# 2021_Design_Sch_PilotCity.net
KiCad netlist of a schematic drawn in EAGLE
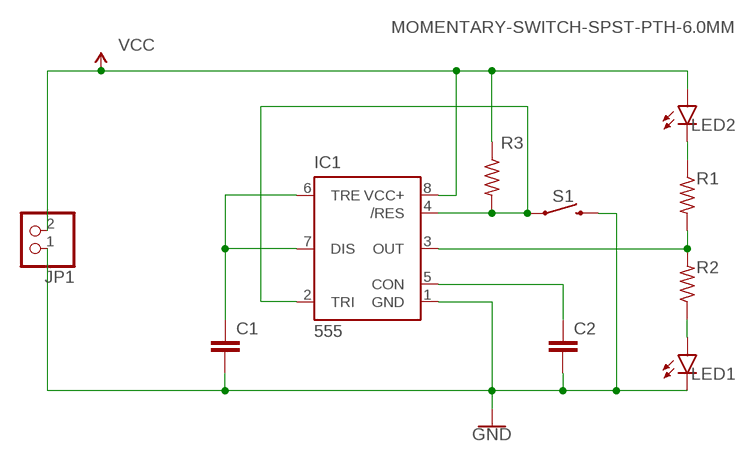
[diagram p0: schematic, sheet 1]

(export (version "E")
  (design (tool "Eeschema 10.0.6"))
  (components
    (comp (ref "C1")
      (value "C5/7.2")
      (footprint "eagle-import:C5B7.2")
      (libsource (lib "eagle-import") (part "C5/7.2"))
    )
    (comp (ref "C2")
      (value "C5/7.2")
      (footprint "eagle-import:C5B7.2")
      (libsource (lib "eagle-import") (part "C5/7.2"))
    )
    (comp (ref "IC1")
      (value "555")
      (footprint "eagle-import:DIP08-KIT")
      (libsource (lib "eagle-import") (part "555KIT"))
    )
    (comp (ref "JP1")
      (value "PINHD-1X2")
      (footprint "eagle-import:1X02")
      (libsource (lib "eagle-import") (part "PINHD-1X2"))
    )
    (comp (ref "LED1")
      (value "LEDB156")
      (footprint "eagle-import:Q62902-B156")
      (libsource (lib "eagle-import") (part "LEDB156"))
    )
    (comp (ref "LED2")
      (value "LEDB156")
      (footprint "eagle-import:Q62902-B156")
      (libsource (lib "eagle-import") (part "LEDB156"))
    )
    (comp (ref "R1")
      (value "R-US_0207/10")
      (footprint "eagle-import:0207_10")
      (libsource (lib "eagle-import") (part "R-US_0207/10"))
    )
    (comp (ref "R2")
      (value "R-US_0207/10")
      (footprint "eagle-import:0207_10")
      (libsource (lib "eagle-import") (part "R-US_0207/10"))
    )
    (comp (ref "R3")
      (value "R-US_0207/10")
      (footprint "eagle-import:0207_10")
      (libsource (lib "eagle-import") (part "R-US_0207/10"))
    )
    (comp (ref "S1")
      (value "MOMENTARY-SWITCH-SPST-PTH-6.0MM")
      (footprint "eagle-import:TACTILE_SWITCH_PTH_6.0MM")
      (libsource (lib "eagle-import") (part "MOMENTARY-SWITCH-SPST-PTH-6.0MM"))
    )
  )
  (nets
    (net (code "1") (name "GND") (class "Default")
      (node (ref "C1") (pin "2") (pinfunction "2_2") (pintype "passive"))
      (node (ref "C2") (pin "2") (pinfunction "2_2") (pintype "passive"))
      (node (ref "IC1") (pin "1") (pinfunction "GND_1") (pintype "power_in"))
      (node (ref "JP1") (pin "1") (pinfunction "1_1") (pintype "passive"))
      (node (ref "LED1") (pin "K") (pinfunction "C_K") (pintype "passive"))
      (node (ref "S1") (pin "3") (pinfunction "2_3") (pintype "passive"))
    )
    (net (code "2") (name "Net-(IC1-CON)") (class "Default")
      (node (ref "C2") (pin "1") (pinfunction "1_1") (pintype "passive"))
      (node (ref "IC1") (pin "5") (pinfunction "CON_5") (pintype "input"))
    )
    (net (code "3") (name "Net-(IC1-DIS)") (class "Default")
      (node (ref "C1") (pin "1") (pinfunction "1_1") (pintype "passive"))
      (node (ref "IC1") (pin "6") (pinfunction "TRE_6") (pintype "input"))
      (node (ref "IC1") (pin "7") (pinfunction "DIS_7") (pintype "input"))
    )
    (net (code "4") (name "Net-(IC1-OUT)") (class "Default")
      (node (ref "IC1") (pin "3") (pinfunction "OUT_3") (pintype "output"))
      (node (ref "R1") (pin "2") (pinfunction "2_2") (pintype "passive"))
      (node (ref "R2") (pin "2") (pinfunction "2_2") (pintype "passive"))
    )
    (net (code "5") (name "Net-(IC1-TRI)") (class "Default")
      (node (ref "IC1") (pin "2") (pinfunction "TRI_2") (pintype "input"))
      (node (ref "IC1") (pin "4") (pinfunction "/RES_4") (pintype "input"))
      (node (ref "R3") (pin "2") (pinfunction "2_2") (pintype "passive"))
      (node (ref "S1") (pin "1") (pinfunction "1_1") (pintype "passive"))
    )
    (net (code "6") (name "Net-(LED1-PadA)") (class "Default")
      (node (ref "LED1") (pin "A") (pinfunction "A_A") (pintype "passive"))
      (node (ref "R2") (pin "1") (pinfunction "1_1") (pintype "passive"))
    )
    (net (code "7") (name "Net-(LED2-C)") (class "Default")
      (node (ref "LED2") (pin "K") (pinfunction "C_K") (pintype "passive"))
      (node (ref "R1") (pin "1") (pinfunction "1_1") (pintype "passive"))
    )
    (net (code "8") (name "VCC") (class "Default")
      (node (ref "IC1") (pin "8") (pinfunction "VCC+_8") (pintype "power_in"))
      (node (ref "JP1") (pin "2") (pinfunction "2_2") (pintype "passive"))
      (node (ref "LED2") (pin "A") (pinfunction "A_A") (pintype "passive"))
      (node (ref "R3") (pin "1") (pinfunction "1_1") (pintype "passive"))
    )
  )
)
